# BMS_Carrier_-_AFE_Interface.net
KiCad netlist of a schematic drawn in Altium Designer
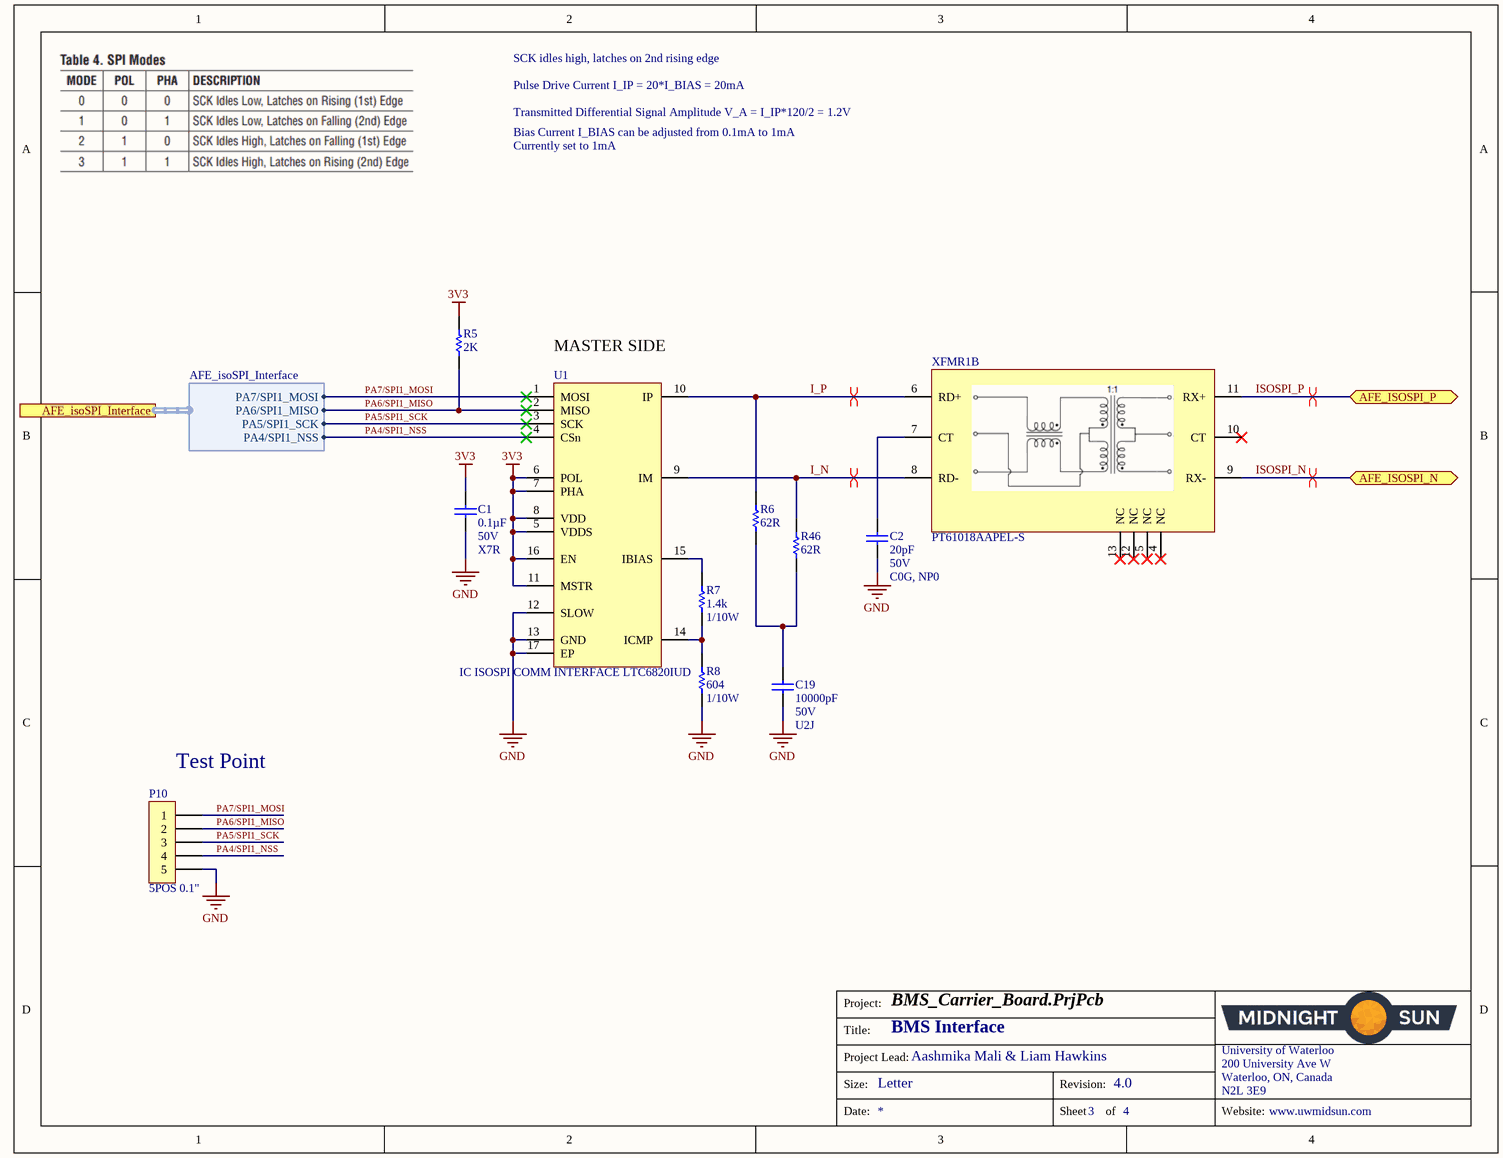
[diagram p0: BMS Carrier - AFE Interface.SchDoc]

(export (version "E")
  (design (tool "Eeschema 10.0.6"))
  (components
    (comp (ref "C1")
      (value "CAP CER 0.1UF 50V 10% X7R 0603")
      (footprint "CAP, 0603")
      (description "0.10µF ±10% 50V Ceramic Capacitor X7R 0603 (1608 Metric)")
      (fields
        (field (name "TOLERANCE") "±10%")
        (field (name "CAPACITANCE") "0.1µF")
        (field (name "VOLTAGE") "50V")
        (field (name "TEMPERATURE COEFFICIENT") "X7R")
      )
      (libsource (lib "Schematic Diagrams") (part "CAP CER 0.1UF 50V 10% X7R 0603"))
    )
    (comp (ref "C2")
      (value "CAP CER 20PF 50V ±5% C0G/NP0 0603")
      (footprint "CAP, 0603")
      (description "20pF ±5% 50V Ceramic Capacitor C0G, NP0 0603 (1608 Metric)")
      (fields
        (field (name "TOLERANCE") "±5%")
        (field (name "CAPACITANCE") "20pF")
        (field (name "VOLTAGE") "50V")
        (field (name "TEMPERATURE COEFFICIENT") "C0G, NP0")
      )
      (libsource (lib "Schematic Diagrams") (part "CAP CER 20PF 50V ±5% C0G/NP0 0603"))
    )
    (comp (ref "C19")
      (value "CAP CER 10nF 50V 5% X7R 0603")
      (footprint "CAP, 0603")
      (description "10000pF ±5% 50V Ceramic Capacitor U2J 0603 (1608 Metric)")
      (fields
        (field (name "TOLERANCE") "±5%")
        (field (name "CAPACITANCE") "10000pF")
        (field (name "VOLTAGE") "50V")
        (field (name "TEMPERATURE COEFFICIENT") "U2J")
      )
      (libsource (lib "Schematic Diagrams") (part "CAP CER 10nF 50V 5% X7R 0603"))
    )
    (comp (ref "P10")
      (value "5POS 0.1\"")
      (footprint "CONN, 5POS HEADR 0.1\"")
      (libsource (lib "Schematic Diagrams") (part "CONN 5POS HEADR MALE 0.1{dblquote}"))
    )
    (comp (ref "R5")
      (value "2K")
      (footprint "RES, 0603")
      (description "2k Ohm ±1% 0.1W, 1/10W Chip Resistor 0603 (1608 Metric) Moisture Resistant Thick Film")
      (fields
        (field (name "MANUFACTURER") "Yageo")
        (field (name "MANUFACTURER PART NUMBER") "RC0603FR-072KL")
      )
      (libsource (lib "Schematic Diagrams") (part "RES 2K OHM 1% 1/10W 0603"))
    )
    (comp (ref "R6")
      (value "62R")
      (footprint "RES, 0603")
      (description "62 Ohms ±0.1% 0.1W, 1/10W Chip Resistor 0603 (1608 Metric) Automotive AEC-Q200 Thin Film")
      (fields
        (field (name "MANUFACTURER") "Panasonic Electronic Components")
        (field (name "MANUFACTURER PART NUMBER") "ERA-3AEB620V")
      )
      (libsource (lib "Schematic Diagrams") (part "RES 62 OHM 0.1% 1/10W 0603"))
    )
    (comp (ref "R7")
      (value "RES 1.4k OHM 1% 1/10W 0603")
      (footprint "RES, 0603")
      (description "RES SMD 1.4K OHM 1% 1/10W 0603")
      (fields
        (field (name "TOLERANCE") "±1%")
        (field (name "RESISTANCE") "1.4k")
        (field (name "POWER") "1/10W")
      )
      (libsource (lib "Schematic Diagrams") (part "RES 1.4k OHM 1% 1/10W 0603"))
    )
    (comp (ref "R8")
      (value "RES 604 OHM 1% 1/10W 0603")
      (footprint "RES, 0603")
      (description "RES SMD 604 OHM 1% 1/10W 0603")
      (fields
        (field (name "TOLERANCE") "±1%")
        (field (name "RESISTANCE") "604")
        (field (name "POWER") "1/10W")
      )
      (libsource (lib "Schematic Diagrams") (part "RES 604 OHM 1% 1/10W 0603"))
    )
    (comp (ref "R46")
      (value "62R")
      (footprint "RES, 0603")
      (description "62 Ohms ±0.1% 0.1W, 1/10W Chip Resistor 0603 (1608 Metric) Automotive AEC-Q200 Thin Film")
      (fields
        (field (name "MANUFACTURER") "Panasonic Electronic Components")
        (field (name "MANUFACTURER PART NUMBER") "ERA-3AEB620V")
      )
      (libsource (lib "Schematic Diagrams") (part "RES 62 OHM 0.1% 1/10W 0603"))
    )
    (comp (ref "U1")
      (value "IC ISOSPI COMM INTERFACE LTC6820IUD")
      (footprint "IC COMM INTERFACE ISOSPI 16-QFN")
      (description "IC COMM INTERFACE ISOSPI 16-QFN")
      (fields
        (field (name "MANUFACTURER") "Linear Technology")
        (field (name "MANUFACTURER PART NUMBER") "LTC6820IUD#PBF")
      )
      (libsource (lib "Schematic Diagrams") (part "IC ISOSPI COMM INTERFACE LTC6820IUD"))
    )
    (comp (ref "XFMR1")
      (value "IC PULSE XFMR 1CT:1CT 350UH SMD")
      (footprint "IC, PULSE XFMR 1CT:1CT 350UH SMD")
      (description "PULSE XFMR 1CT:1CT 350UH SMD")
      (fields (field (name "MANUFACTURER") "Bourns Inc.") (field (name "MFG_PN") "PT61018AAPEL-S"))
      (libsource (lib "Schematic Diagrams") (part "IC PULSE XFMR 1CT{colon}1CT 350UH SMD"))
    )
  )
  (nets
    (net (code "2") (name "/ISOSPI_N") (class "Default")
      (node (ref "XFMR1") (pin "9") (pinfunction "RX-_9") (pintype "passive"))
    )
    (net (code "3") (name "/ISOSPI_P") (class "Default")
      (node (ref "XFMR1") (pin "11") (pinfunction "RX+_11") (pintype "passive"))
    )
    (net (code "4") (name "/I_N") (class "Default")
      (node (ref "R46") (pin "1") (pinfunction "1_1") (pintype "passive"))
      (node (ref "U1") (pin "9") (pinfunction "IM_9") (pintype "passive"))
      (node (ref "XFMR1") (pin "8") (pinfunction "RD-_8") (pintype "passive"))
    )
    (net (code "5") (name "/I_P") (class "Default")
      (node (ref "R6") (pin "1") (pinfunction "1_1") (pintype "passive"))
      (node (ref "U1") (pin "10") (pinfunction "IP_10") (pintype "passive"))
      (node (ref "XFMR1") (pin "6") (pinfunction "RD+_6") (pintype "passive"))
    )
    (net (code "6") (name "/PA4{slash}SPI1_NSS") (class "Default")
      (node (ref "P10") (pin "4") (pinfunction "4_4") (pintype "passive"))
      (node (ref "U1") (pin "4") (pinfunction "CSn_4") (pintype "passive"))
    )
    (net (code "7") (name "/PA5{slash}SPI1_SCK") (class "Default")
      (node (ref "P10") (pin "3") (pinfunction "3_3") (pintype "passive"))
      (node (ref "U1") (pin "3") (pinfunction "SCK_3") (pintype "passive"))
    )
    (net (code "8") (name "/PA6{slash}SPI1_MISO") (class "Default")
      (node (ref "P10") (pin "2") (pinfunction "2_2") (pintype "passive"))
      (node (ref "R5") (pin "2") (pinfunction "2_2") (pintype "passive"))
      (node (ref "U1") (pin "2") (pinfunction "MISO_2") (pintype "passive"))
    )
    (net (code "9") (name "/PA7{slash}SPI1_MOSI") (class "Default")
      (node (ref "P10") (pin "1") (pinfunction "1_1") (pintype "passive"))
      (node (ref "U1") (pin "1") (pinfunction "MOSI_1") (pintype "passive"))
    )
    (net (code "11") (name "3V3") (class "Default")
      (node (ref "C1") (pin "1") (pinfunction "1_1") (pintype "passive"))
      (node (ref "R5") (pin "1") (pinfunction "1_1") (pintype "passive"))
      (node (ref "U1") (pin "11") (pinfunction "MSTR_11") (pintype "passive"))
      (node (ref "U1") (pin "16") (pinfunction "EN_16") (pintype "passive"))
      (node (ref "U1") (pin "5") (pinfunction "VDDS_5") (pintype "passive"))
      (node (ref "U1") (pin "6") (pinfunction "POL_6") (pintype "passive"))
      (node (ref "U1") (pin "7") (pinfunction "PHA_7") (pintype "passive"))
      (node (ref "U1") (pin "8") (pinfunction "VDD_8") (pintype "passive"))
    )
    (net (code "12") (name "GND") (class "Default")
      (node (ref "C1") (pin "2") (pinfunction "2_2") (pintype "passive"))
      (node (ref "C19") (pin "2") (pinfunction "2_2") (pintype "passive"))
      (node (ref "C2") (pin "2") (pinfunction "2_2") (pintype "passive"))
      (node (ref "P10") (pin "5") (pinfunction "5_5") (pintype "passive"))
      (node (ref "R8") (pin "2") (pinfunction "2_2") (pintype "passive"))
      (node (ref "U1") (pin "12") (pinfunction "SLOW_12") (pintype "passive"))
      (node (ref "U1") (pin "13") (pinfunction "GND_13") (pintype "passive"))
      (node (ref "U1") (pin "17") (pinfunction "EP_17") (pintype "passive"))
    )
    (net (code "13") (name "Net-(C2-Pad1)") (class "Default")
      (node (ref "C2") (pin "1") (pinfunction "1_1") (pintype "passive"))
      (node (ref "XFMR1") (pin "7") (pinfunction "CT_7") (pintype "passive"))
    )
    (net (code "14") (name "Net-(C19-Pad1)") (class "Default")
      (node (ref "C19") (pin "1") (pinfunction "1_1") (pintype "passive"))
      (node (ref "R46") (pin "2") (pinfunction "2_2") (pintype "passive"))
      (node (ref "R6") (pin "2") (pinfunction "2_2") (pintype "passive"))
    )
    (net (code "15") (name "Net-(U1-IBIAS)") (class "Default")
      (node (ref "R7") (pin "1") (pinfunction "1_1") (pintype "passive"))
      (node (ref "U1") (pin "15") (pinfunction "IBIAS_15") (pintype "passive"))
    )
    (net (code "16") (name "Net-(U1-ICMP)") (class "Default")
      (node (ref "R7") (pin "2") (pinfunction "2_2") (pintype "passive"))
      (node (ref "R8") (pin "1") (pinfunction "1_1") (pintype "passive"))
      (node (ref "U1") (pin "14") (pinfunction "ICMP_14") (pintype "passive"))
    )
    (net (code "17") (name "unconnected-(XFMR1B-CT-Pad10)") (class "Default")
      (node (ref "XFMR1") (pin "10") (pinfunction "CT_10") (pintype "passive+no_connect"))
    )
    (net (code "18") (name "unconnected-(XFMR1B-NC-Pad4)") (class "Default")
      (node (ref "XFMR1") (pin "4") (pinfunction "NC_4") (pintype "passive+no_connect"))
    )
    (net (code "19") (name "unconnected-(XFMR1B-NC-Pad5)") (class "Default")
      (node (ref "XFMR1") (pin "5") (pinfunction "NC_5") (pintype "passive+no_connect"))
    )
    (net (code "20") (name "unconnected-(XFMR1B-NC-Pad12)") (class "Default")
      (node (ref "XFMR1") (pin "12") (pinfunction "NC_12") (pintype "passive+no_connect"))
    )
    (net (code "21") (name "unconnected-(XFMR1B-NC-Pad13)") (class "Default")
      (node (ref "XFMR1") (pin "13") (pinfunction "NC_13") (pintype "passive+no_connect"))
    )
  )
)
